# SCH_ethan-stick_2025-04-03.net
KiCad netlist of a schematic drawn in EasyEDA
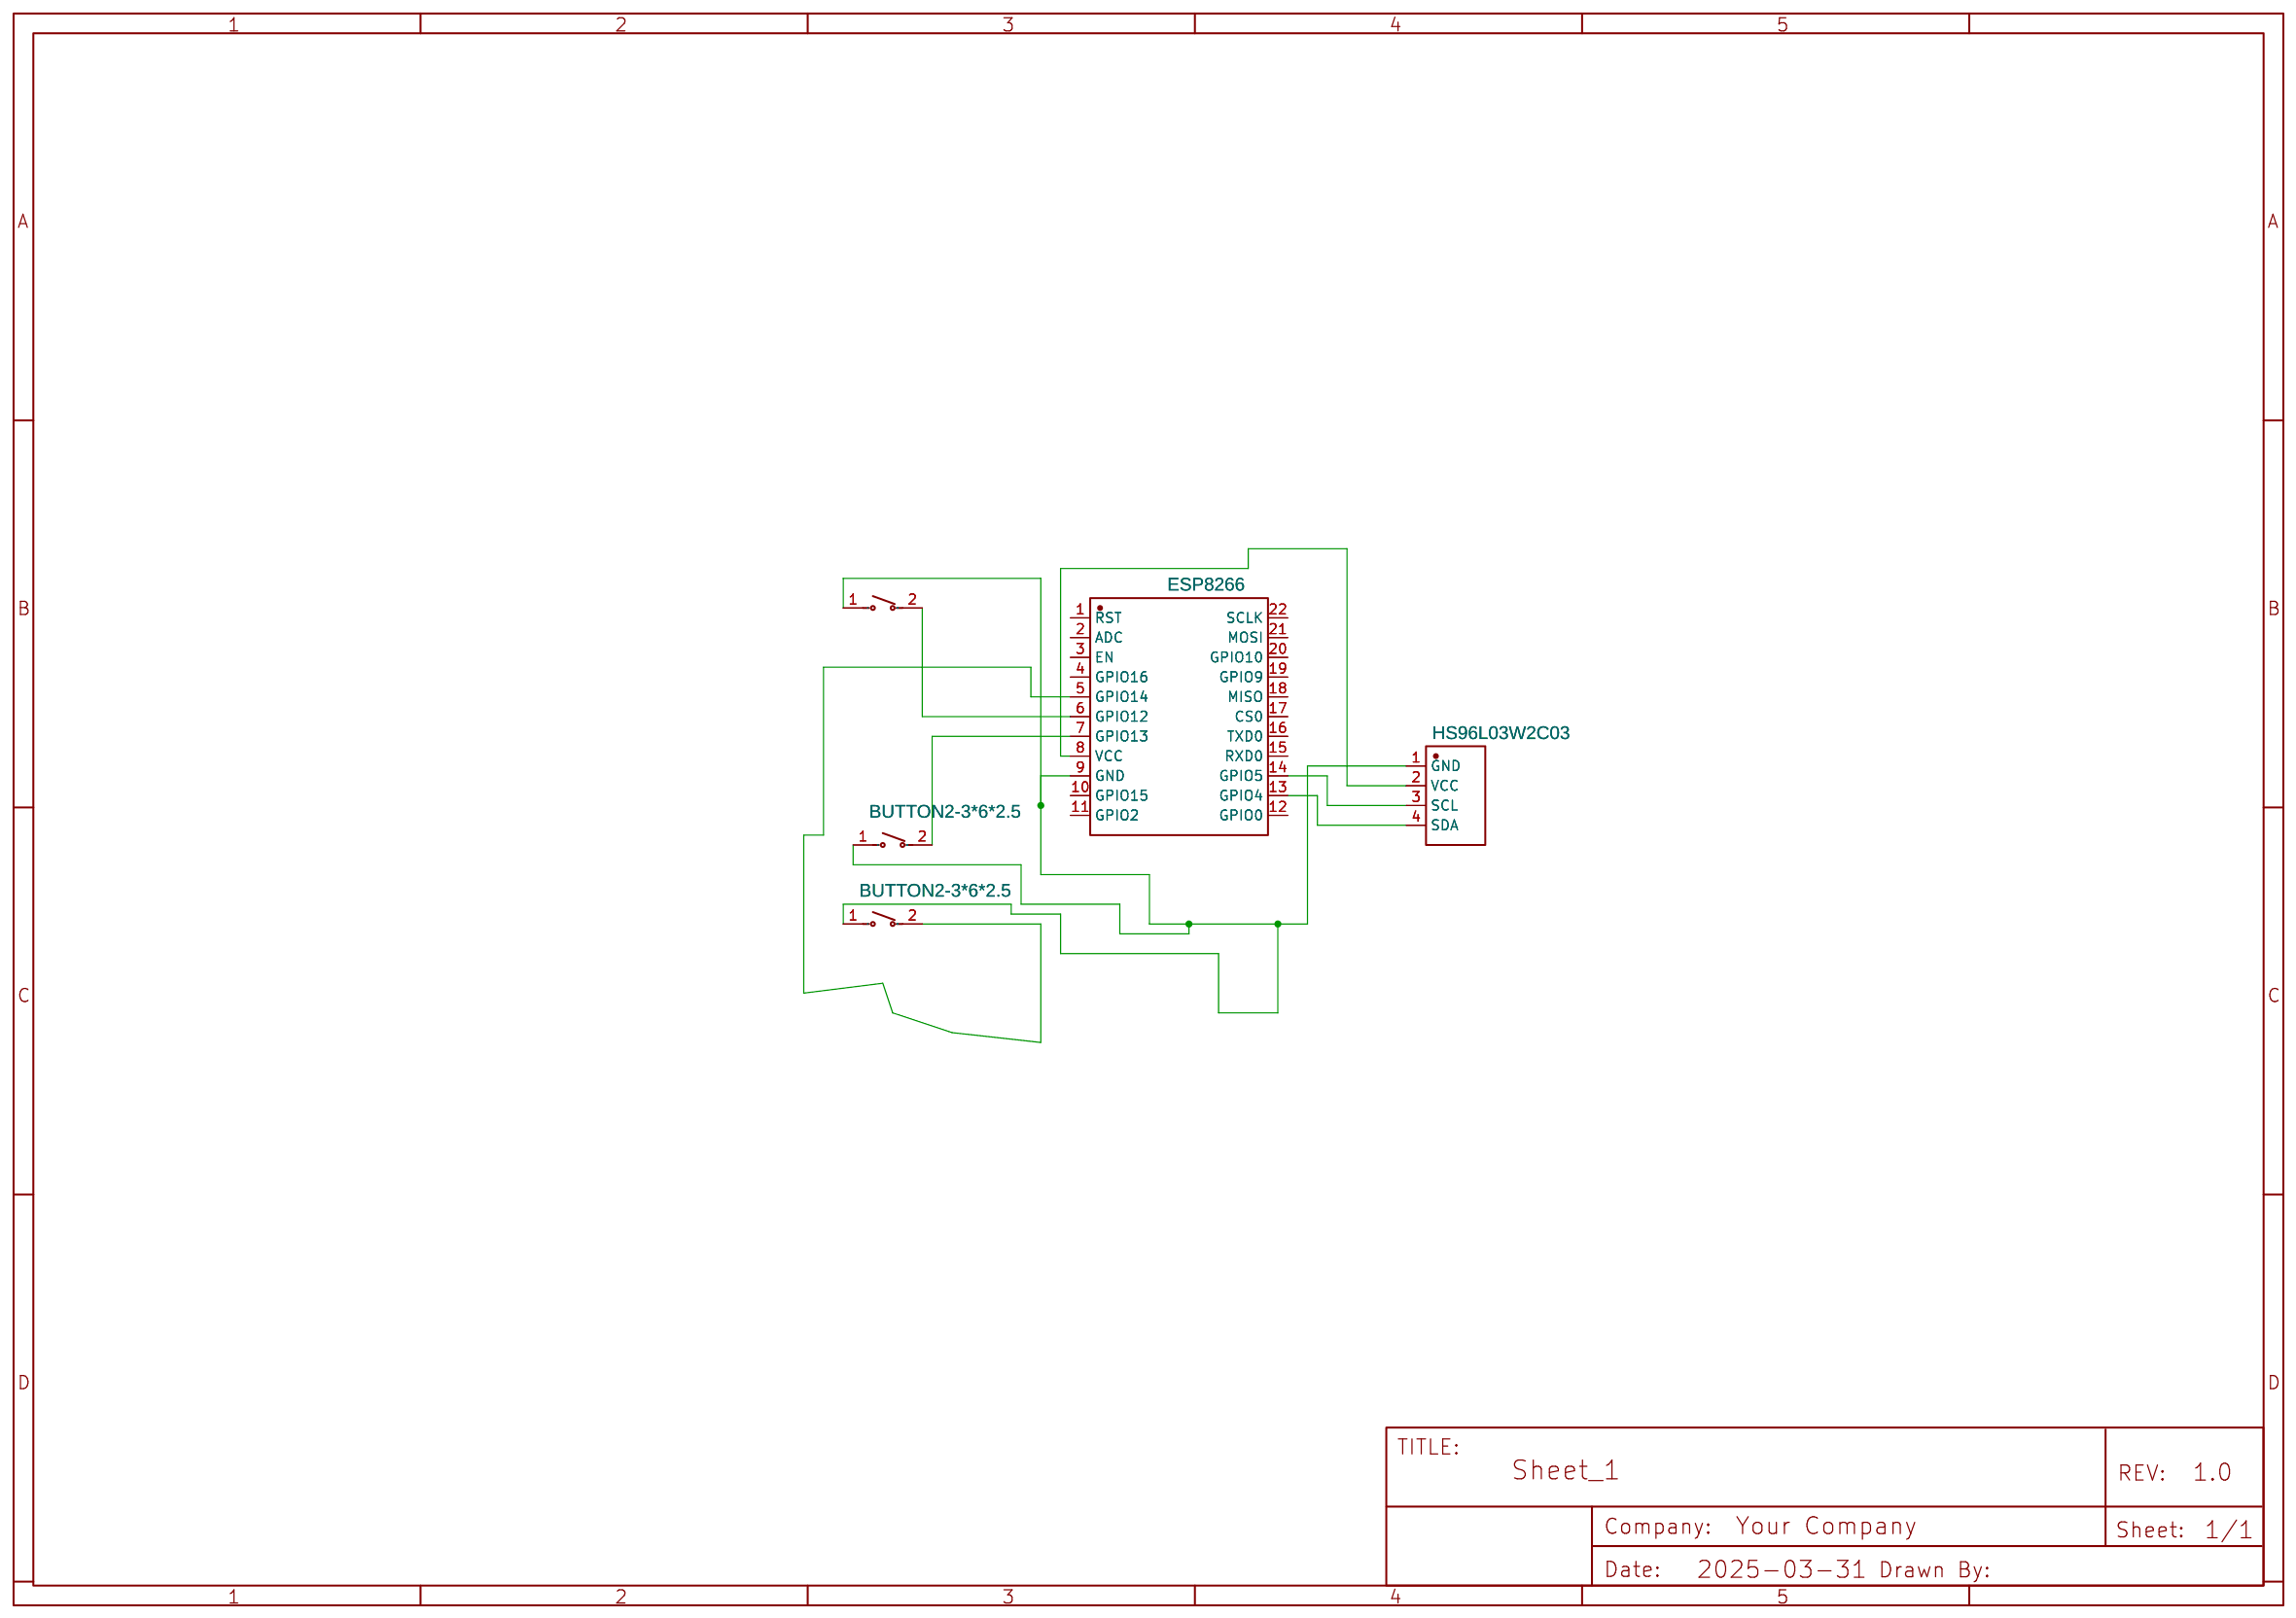
[diagram p0: schematic sheet]

(export (version "E")
  (design (tool "Eeschema 10.0.6"))
  (components
    (comp (ref "KEY1") (value "BUTTON2-3*6*2.5") (libsource (lib "") (part "BUTTON2-3*6*2.5")))
    (comp (ref "KEY2") (value "BUTTON2-3*6*2.5") (libsource (lib "") (part "BUTTON2-3*6*2.5")))
    (comp (ref "KEY3") (value "BUTTON2-3*6*2.5") (libsource (lib "") (part "BUTTON2-3*6*2.5")))
    (comp (ref "U1") (value "ESP8266") (libsource (lib "") (part "ESP8266")))
    (comp (ref "U2")
      (value "HS96L03W2C03")
      (fields (field (name "Manufacturer") "HS(汉昇)"))
      (libsource (lib "") (part "HS96L03W2C03"))
    )
  )
  (nets
    (net (code "1") (name "Net-(U1-GND)") (class "Default")
      (node (ref "KEY1") (pin "1") (pinfunction "1_1") (pintype "unspecified"))
      (node (ref "KEY2") (pin "1") (pinfunction "1_1") (pintype "unspecified"))
      (node (ref "KEY3") (pin "1") (pinfunction "1_1") (pintype "unspecified"))
      (node (ref "U1") (pin "9") (pinfunction "GND_9") (pintype "unspecified"))
      (node (ref "U2") (pin "1") (pinfunction "GND_1") (pintype "unspecified"))
    )
    (net (code "2") (name "Net-(U1-GPIO4)") (class "Default")
      (node (ref "U1") (pin "13") (pinfunction "GPIO4_13") (pintype "unspecified"))
      (node (ref "U2") (pin "4") (pinfunction "SDA_4") (pintype "unspecified"))
    )
    (net (code "3") (name "Net-(U1-GPIO5)") (class "Default")
      (node (ref "U1") (pin "14") (pinfunction "GPIO5_14") (pintype "unspecified"))
      (node (ref "U2") (pin "3") (pinfunction "SCL_3") (pintype "unspecified"))
    )
    (net (code "4") (name "Net-(U1-GPIO12)") (class "Default")
      (node (ref "KEY1") (pin "2") (pinfunction "2_2") (pintype "unspecified"))
      (node (ref "U1") (pin "6") (pinfunction "GPIO12_6") (pintype "unspecified"))
    )
    (net (code "5") (name "Net-(U1-GPIO13)") (class "Default")
      (node (ref "KEY2") (pin "2") (pinfunction "2_2") (pintype "unspecified"))
      (node (ref "U1") (pin "7") (pinfunction "GPIO13_7") (pintype "unspecified"))
    )
    (net (code "6") (name "Net-(U1-GPIO14)") (class "Default")
      (node (ref "KEY3") (pin "2") (pinfunction "2_2") (pintype "unspecified"))
      (node (ref "U1") (pin "5") (pinfunction "GPIO14_5") (pintype "unspecified"))
    )
    (net (code "7") (name "Net-(U1-VCC)") (class "Default")
      (node (ref "U1") (pin "8") (pinfunction "VCC_8") (pintype "unspecified"))
      (node (ref "U2") (pin "2") (pinfunction "VCC_2") (pintype "unspecified"))
    )
    (net (code "8") (name "unconnected-(U1-ADC-Pad2)") (class "Default")
      (node (ref "U1") (pin "2") (pinfunction "ADC_2") (pintype "unspecified"))
    )
    (net (code "9") (name "unconnected-(U1-CS0-Pad17)") (class "Default")
      (node (ref "U1") (pin "17") (pinfunction "CS0_17") (pintype "unspecified"))
    )
    (net (code "10") (name "unconnected-(U1-EN-Pad3)") (class "Default")
      (node (ref "U1") (pin "3") (pinfunction "EN_3") (pintype "unspecified"))
    )
    (net (code "11") (name "unconnected-(U1-GPIO0-Pad12)") (class "Default")
      (node (ref "U1") (pin "12") (pinfunction "GPIO0_12") (pintype "unspecified"))
    )
    (net (code "12") (name "unconnected-(U1-GPIO2-Pad11)") (class "Default")
      (node (ref "U1") (pin "11") (pinfunction "GPIO2_11") (pintype "unspecified"))
    )
    (net (code "13") (name "unconnected-(U1-GPIO9-Pad19)") (class "Default")
      (node (ref "U1") (pin "19") (pinfunction "GPIO9_19") (pintype "unspecified"))
    )
    (net (code "14") (name "unconnected-(U1-GPIO10-Pad20)") (class "Default")
      (node (ref "U1") (pin "20") (pinfunction "GPIO10_20") (pintype "unspecified"))
    )
    (net (code "15") (name "unconnected-(U1-GPIO15-Pad10)") (class "Default")
      (node (ref "U1") (pin "10") (pinfunction "GPIO15_10") (pintype "unspecified"))
    )
    (net (code "16") (name "unconnected-(U1-GPIO16-Pad4)") (class "Default")
      (node (ref "U1") (pin "4") (pinfunction "GPIO16_4") (pintype "unspecified"))
    )
    (net (code "17") (name "unconnected-(U1-MISO-Pad18)") (class "Default")
      (node (ref "U1") (pin "18") (pinfunction "MISO_18") (pintype "unspecified"))
    )
    (net (code "18") (name "unconnected-(U1-MOSI-Pad21)") (class "Default")
      (node (ref "U1") (pin "21") (pinfunction "MOSI_21") (pintype "unspecified"))
    )
    (net (code "19") (name "unconnected-(U1-RST-Pad1)") (class "Default")
      (node (ref "U1") (pin "1") (pinfunction "RST_1") (pintype "unspecified"))
    )
    (net (code "20") (name "unconnected-(U1-RXD0-Pad15)") (class "Default")
      (node (ref "U1") (pin "15") (pinfunction "RXD0_15") (pintype "unspecified"))
    )
    (net (code "21") (name "unconnected-(U1-SCLK-Pad22)") (class "Default")
      (node (ref "U1") (pin "22") (pinfunction "SCLK_22") (pintype "unspecified"))
    )
    (net (code "22") (name "unconnected-(U1-TXD0-Pad16)") (class "Default")
      (node (ref "U1") (pin "16") (pinfunction "TXD0_16") (pintype "unspecified"))
    )
  )
)
